# 06_-_PERIPHERALS_A.net
KiCad netlist of a schematic drawn in Altium Designer
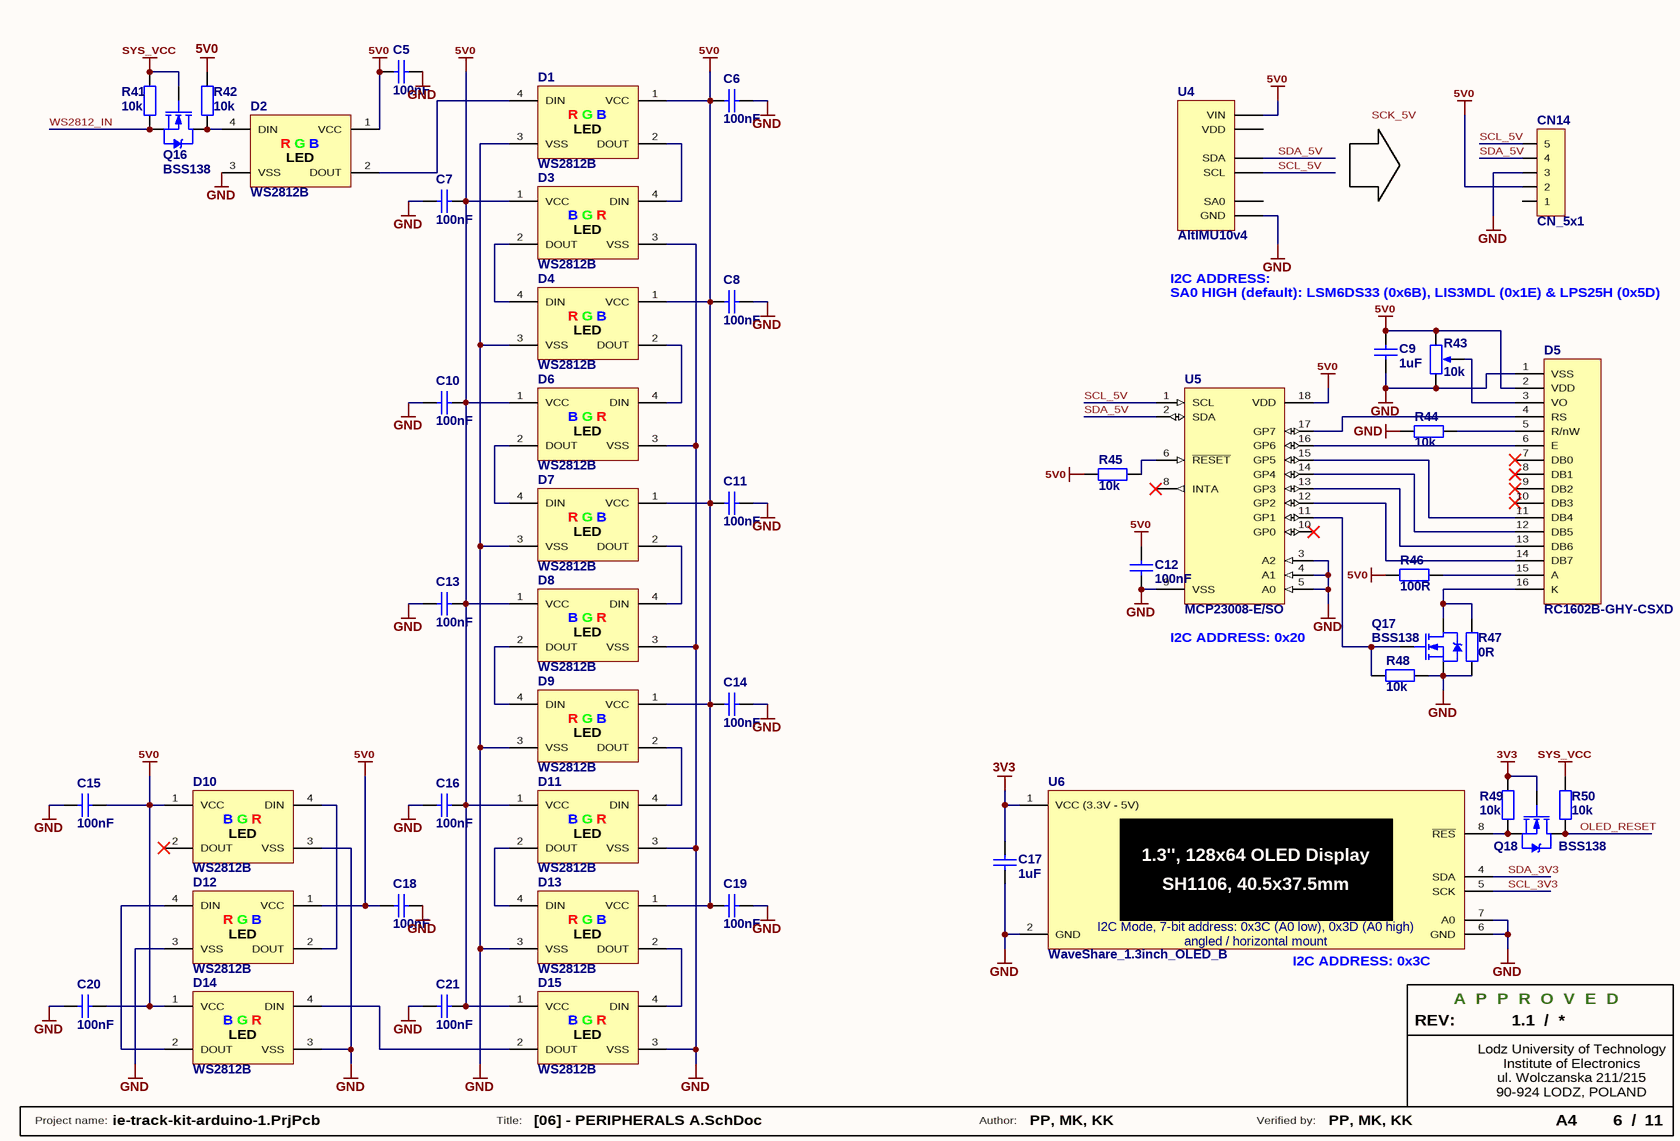
[diagram p0: [06] - PERIPHERALS A.SchDoc]

(export (version "E")
  (design (tool "Eeschema 10.0.6"))
  (components
    (comp (ref "C5")
      (value "100nF")
      (footprint "C0805")
      (description "Capacitor")
      (libsource (lib "capacitors") (part "Cap"))
    )
    (comp (ref "C6")
      (value "100nF")
      (footprint "C0805")
      (description "Capacitor")
      (libsource (lib "capacitors") (part "Cap"))
    )
    (comp (ref "C7")
      (value "100nF")
      (footprint "C0805")
      (description "Capacitor")
      (libsource (lib "capacitors") (part "Cap"))
    )
    (comp (ref "C8")
      (value "100nF")
      (footprint "C0805")
      (description "Capacitor")
      (libsource (lib "capacitors") (part "Cap"))
    )
    (comp (ref "C9")
      (value "1uF")
      (footprint "C0805")
      (description "Capacitor")
      (libsource (lib "capacitors") (part "Cap"))
    )
    (comp (ref "C10")
      (value "100nF")
      (footprint "C0805")
      (description "Capacitor")
      (libsource (lib "capacitors") (part "Cap"))
    )
    (comp (ref "C11")
      (value "100nF")
      (footprint "C0805")
      (description "Capacitor")
      (libsource (lib "capacitors") (part "Cap"))
    )
    (comp (ref "C12")
      (value "100nF")
      (footprint "C0805")
      (description "Capacitor")
      (libsource (lib "capacitors") (part "Cap"))
    )
    (comp (ref "C13")
      (value "100nF")
      (footprint "C0805")
      (description "Capacitor")
      (libsource (lib "capacitors") (part "Cap"))
    )
    (comp (ref "C14")
      (value "100nF")
      (footprint "C0805")
      (description "Capacitor")
      (libsource (lib "capacitors") (part "Cap"))
    )
    (comp (ref "C15")
      (value "100nF")
      (footprint "C0805")
      (description "Capacitor")
      (libsource (lib "capacitors") (part "Cap"))
    )
    (comp (ref "C16")
      (value "100nF")
      (footprint "C0805")
      (description "Capacitor")
      (libsource (lib "capacitors") (part "Cap"))
    )
    (comp (ref "C17")
      (value "1uF")
      (footprint "C0805")
      (description "Capacitor")
      (libsource (lib "capacitors") (part "Cap"))
    )
    (comp (ref "C18")
      (value "100nF")
      (footprint "C0805")
      (description "Capacitor")
      (libsource (lib "capacitors") (part "Cap"))
    )
    (comp (ref "C19")
      (value "100nF")
      (footprint "C0805")
      (description "Capacitor")
      (libsource (lib "capacitors") (part "Cap"))
    )
    (comp (ref "C20")
      (value "100nF")
      (footprint "C0805")
      (description "Capacitor")
      (libsource (lib "capacitors") (part "Cap"))
    )
    (comp (ref "C21")
      (value "100nF")
      (footprint "C0805")
      (description "Capacitor")
      (libsource (lib "capacitors") (part "Cap"))
    )
    (comp (ref "CN14")
      (value "CN_5x1")
      (footprint "GP_5x1H_F")
      (libsource (lib "goldpin_female") (part "CN_5x1"))
    )
    (comp (ref "D1")
      (value "WS2812B")
      (footprint "WS2812B")
      (description "Intelligent control LED integrated light source")
      (libsource (lib "leds") (part "WS2812B"))
    )
    (comp (ref "D2")
      (value "WS2812B")
      (footprint "WS2812B")
      (description "Intelligent control LED integrated light source")
      (libsource (lib "leds") (part "WS2812B"))
    )
    (comp (ref "D3")
      (value "WS2812B")
      (footprint "WS2812B")
      (description "Intelligent control LED integrated light source")
      (libsource (lib "") (part "WS2812B_1"))
    )
    (comp (ref "D4")
      (value "WS2812B")
      (footprint "WS2812B")
      (description "Intelligent control LED integrated light source")
      (libsource (lib "leds") (part "WS2812B"))
    )
    (comp (ref "D5")
      (value "RC1602B-GHY-CSXD")
      (footprint "RC1602B-GHY-CSXD")
      (description "16x2 LCD Display")
      (libsource (lib "lcd_displays") (part "RC1602B-GHY-CSXD"))
    )
    (comp (ref "D6")
      (value "WS2812B")
      (footprint "WS2812B")
      (description "Intelligent control LED integrated light source")
      (libsource (lib "") (part "WS2812B_1"))
    )
    (comp (ref "D7")
      (value "WS2812B")
      (footprint "WS2812B")
      (description "Intelligent control LED integrated light source")
      (libsource (lib "leds") (part "WS2812B"))
    )
    (comp (ref "D8")
      (value "WS2812B")
      (footprint "WS2812B")
      (description "Intelligent control LED integrated light source")
      (libsource (lib "") (part "WS2812B_1"))
    )
    (comp (ref "D9")
      (value "WS2812B")
      (footprint "WS2812B")
      (description "Intelligent control LED integrated light source")
      (libsource (lib "leds") (part "WS2812B"))
    )
    (comp (ref "D10")
      (value "WS2812B")
      (footprint "WS2812B")
      (description "Intelligent control LED integrated light source")
      (libsource (lib "") (part "WS2812B_1"))
    )
    (comp (ref "D11")
      (value "WS2812B")
      (footprint "WS2812B")
      (description "Intelligent control LED integrated light source")
      (libsource (lib "") (part "WS2812B_1"))
    )
    (comp (ref "D12")
      (value "WS2812B")
      (footprint "WS2812B")
      (description "Intelligent control LED integrated light source")
      (libsource (lib "leds") (part "WS2812B"))
    )
    (comp (ref "D13")
      (value "WS2812B")
      (footprint "WS2812B")
      (description "Intelligent control LED integrated light source")
      (libsource (lib "leds") (part "WS2812B"))
    )
    (comp (ref "D14")
      (value "WS2812B")
      (footprint "WS2812B")
      (description "Intelligent control LED integrated light source")
      (libsource (lib "") (part "WS2812B_1"))
    )
    (comp (ref "D15")
      (value "WS2812B")
      (footprint "WS2812B")
      (description "Intelligent control LED integrated light source")
      (libsource (lib "") (part "WS2812B_1"))
    )
    (comp (ref "Q16")
      (value "BSS138")
      (footprint "SOT-23")
      (description "N-Channel Enhancement Mode Vertical DMOS FET")
      (fields (field (name "PUBLISHER") "Altium Limited"))
      (libsource (lib "transistors_other") (part "BSS138"))
    )
    (comp (ref "Q17")
      (value "BSS138")
      (footprint "SOT-23")
      (description "N-Channel Enhancement Mode Vertical DMOS FET")
      (fields (field (name "PUBLISHER") "Altium Limited"))
      (libsource (lib "transistors_other") (part "BSS138"))
    )
    (comp (ref "Q18")
      (value "BSS138")
      (footprint "SOT-23")
      (description "N-Channel Enhancement Mode Vertical DMOS FET")
      (fields (field (name "PUBLISHER") "Altium Limited"))
      (libsource (lib "transistors_other") (part "BSS138"))
    )
    (comp (ref "R41")
      (value "10k")
      (footprint "R0805")
      (description "Resistor")
      (libsource (lib "") (part "Res_2"))
    )
    (comp (ref "R42")
      (value "10k")
      (footprint "R0805")
      (description "Resistor")
      (libsource (lib "") (part "Res_2"))
    )
    (comp (ref "R43")
      (value "10k")
      (footprint "3305SMD")
      (description "3305SMD-10K")
      (libsource (lib "resistors") (part "3305SMD-10K"))
    )
    (comp (ref "R44")
      (value "10k")
      (footprint "R0805")
      (description "Resistor")
      (libsource (lib "resistors") (part "Res"))
    )
    (comp (ref "R45")
      (value "10k")
      (footprint "R0805")
      (description "Resistor")
      (libsource (lib "resistors") (part "Res"))
    )
    (comp (ref "R46")
      (value "100R")
      (footprint "R0805")
      (description "Resistor")
      (libsource (lib "resistors") (part "Res"))
    )
    (comp (ref "R47")
      (value "0R")
      (footprint "R0805")
      (description "Resistor")
      (libsource (lib "") (part "Res_1"))
    )
    (comp (ref "R48")
      (value "10k")
      (footprint "R0805")
      (description "Resistor")
      (libsource (lib "resistors") (part "Res"))
    )
    (comp (ref "R49")
      (value "10k")
      (footprint "R0805")
      (description "Resistor")
      (libsource (lib "") (part "Res_2"))
    )
    (comp (ref "R50")
      (value "10k")
      (footprint "R0805")
      (description "Resistor")
      (libsource (lib "") (part "Res_2"))
    )
    (comp (ref "U4")
      (value "AltIMU10v4")
      (footprint "AltIMU-10 v4_REVERSE")
      (description "Pololu Gyro, Accelerometer, Compass, and Altimeter (L3GD20H, LSM303D, and LPS25H Carrier)")
      (libsource (lib "mems_and_imu_modules") (part "AltIMU10v4"))
    )
    (comp (ref "U5")
      (value "MCP23008-E/SO")
      (footprint "SO18W")
      (description "8-Bit I/O Expander with Serial Interface I2C, 18-Pin SOIC Package")
      (libsource (lib "io_expanders") (part "MCP23008-E/SO"))
    )
    (comp (ref "U6")
      (value "WaveShare_1.3inch_OLED_B")
      (footprint "WaveShare_1.3INCH_OLED")
      (description "DEP096032B-W OLED Display")
      (libsource (lib "oled_displays") (part "WaveShare_1.3inch_OLED"))
    )
  )
  (nets
    (net (code "1") (name "/OLED_RESET") (class "Default")
      (node (ref "Q18") (pin "3") (pinfunction "D_3") (pintype "passive"))
      (node (ref "R50") (pin "1") (pinfunction "1_1") (pintype "passive"))
    )
    (net (code "3") (name "/SCL_3V3") (class "Default")
      (node (ref "U6") (pin "5") (pinfunction "SCK_5") (pintype "passive"))
    )
    (net (code "4") (name "/SCL_5V") (class "Default")
      (node (ref "CN14") (pin "5") (pinfunction "5_5") (pintype "passive"))
      (node (ref "U4") (pin "6") (pinfunction "SCL_6") (pintype "passive"))
      (node (ref "U5") (pin "1") (pinfunction "SCL_1") (pintype "input"))
    )
    (net (code "5") (name "/SDA_3V3") (class "Default")
      (node (ref "U6") (pin "4") (pinfunction "SDA_4") (pintype "passive"))
    )
    (net (code "6") (name "/SDA_5V") (class "Default")
      (node (ref "CN14") (pin "4") (pinfunction "4_4") (pintype "passive"))
      (node (ref "U4") (pin "5") (pinfunction "SDA_5") (pintype "passive"))
      (node (ref "U5") (pin "2") (pinfunction "SDA_2") (pintype "bidirectional"))
    )
    (net (code "7") (name "/WS2812_IN") (class "Default")
      (node (ref "Q16") (pin "2") (pinfunction "S_2") (pintype "passive"))
      (node (ref "R41") (pin "1") (pinfunction "1_1") (pintype "passive"))
    )
    (net (code "8") (name "3V3") (class "Default")
      (node (ref "C17") (pin "2") (pinfunction "2_2") (pintype "passive"))
      (node (ref "Q18") (pin "1") (pinfunction "G_1") (pintype "passive"))
      (node (ref "R49") (pin "2") (pinfunction "2_2") (pintype "passive"))
      (node (ref "U6") (pin "1") (pinfunction "VCC_(3.3V_-_5V)_1") (pintype "passive"))
    )
    (net (code "9") (name "5V0") (class "Default")
      (node (ref "C10") (pin "2") (pinfunction "2_2") (pintype "passive"))
      (node (ref "C11") (pin "1") (pinfunction "1_1") (pintype "passive"))
      (node (ref "C12") (pin "2") (pinfunction "2_2") (pintype "passive"))
      (node (ref "C13") (pin "2") (pinfunction "2_2") (pintype "passive"))
      (node (ref "C14") (pin "1") (pinfunction "1_1") (pintype "passive"))
      (node (ref "C15") (pin "2") (pinfunction "2_2") (pintype "passive"))
      (node (ref "C16") (pin "2") (pinfunction "2_2") (pintype "passive"))
      (node (ref "C18") (pin "1") (pinfunction "1_1") (pintype "passive"))
      (node (ref "C19") (pin "1") (pinfunction "1_1") (pintype "passive"))
      (node (ref "C20") (pin "2") (pinfunction "2_2") (pintype "passive"))
      (node (ref "C21") (pin "2") (pinfunction "2_2") (pintype "passive"))
      (node (ref "C5") (pin "1") (pinfunction "1_1") (pintype "passive"))
      (node (ref "C6") (pin "1") (pinfunction "1_1") (pintype "passive"))
      (node (ref "C7") (pin "2") (pinfunction "2_2") (pintype "passive"))
      (node (ref "C8") (pin "1") (pinfunction "1_1") (pintype "passive"))
      (node (ref "C9") (pin "2") (pinfunction "2_2") (pintype "passive"))
      (node (ref "CN14") (pin "2") (pinfunction "2_2") (pintype "passive"))
      (node (ref "D1") (pin "1") (pinfunction "VCC_1") (pintype "power_in"))
      (node (ref "D10") (pin "1") (pinfunction "VCC_1") (pintype "power_in"))
      (node (ref "D11") (pin "1") (pinfunction "VCC_1") (pintype "power_in"))
      (node (ref "D12") (pin "1") (pinfunction "VCC_1") (pintype "power_in"))
      (node (ref "D13") (pin "1") (pinfunction "VCC_1") (pintype "power_in"))
      (node (ref "D14") (pin "1") (pinfunction "VCC_1") (pintype "power_in"))
      (node (ref "D15") (pin "1") (pinfunction "VCC_1") (pintype "power_in"))
      (node (ref "D2") (pin "1") (pinfunction "VCC_1") (pintype "power_in"))
      (node (ref "D3") (pin "1") (pinfunction "VCC_1") (pintype "power_in"))
      (node (ref "D4") (pin "1") (pinfunction "VCC_1") (pintype "power_in"))
      (node (ref "D5") (pin "2") (pinfunction "VDD_2") (pintype "power_in"))
      (node (ref "D6") (pin "1") (pinfunction "VCC_1") (pintype "power_in"))
      (node (ref "D7") (pin "1") (pinfunction "VCC_1") (pintype "power_in"))
      (node (ref "D8") (pin "1") (pinfunction "VCC_1") (pintype "power_in"))
      (node (ref "D9") (pin "1") (pinfunction "VCC_1") (pintype "power_in"))
      (node (ref "R42") (pin "2") (pinfunction "2_2") (pintype "passive"))
      (node (ref "R43") (pin "1") (pinfunction "TOP_1") (pintype "passive"))
      (node (ref "R45") (pin "1") (pinfunction "1_1") (pintype "passive"))
      (node (ref "R46") (pin "1") (pinfunction "1_1") (pintype "passive"))
      (node (ref "U4") (pin "3") (pinfunction "VIN_3") (pintype "passive"))
      (node (ref "U5") (pin "18") (pinfunction "VDD_18") (pintype "power_in"))
    )
    (net (code "10") (name "GND") (class "Default")
      (node (ref "C10") (pin "1") (pinfunction "1_1") (pintype "passive"))
      (node (ref "C11") (pin "2") (pinfunction "2_2") (pintype "passive"))
      (node (ref "C12") (pin "1") (pinfunction "1_1") (pintype "passive"))
      (node (ref "C13") (pin "1") (pinfunction "1_1") (pintype "passive"))
      (node (ref "C14") (pin "2") (pinfunction "2_2") (pintype "passive"))
      (node (ref "C15") (pin "1") (pinfunction "1_1") (pintype "passive"))
      (node (ref "C16") (pin "1") (pinfunction "1_1") (pintype "passive"))
      (node (ref "C17") (pin "1") (pinfunction "1_1") (pintype "passive"))
      (node (ref "C18") (pin "2") (pinfunction "2_2") (pintype "passive"))
      (node (ref "C19") (pin "2") (pinfunction "2_2") (pintype "passive"))
      (node (ref "C20") (pin "1") (pinfunction "1_1") (pintype "passive"))
      (node (ref "C21") (pin "1") (pinfunction "1_1") (pintype "passive"))
      (node (ref "C5") (pin "2") (pinfunction "2_2") (pintype "passive"))
      (node (ref "C6") (pin "2") (pinfunction "2_2") (pintype "passive"))
      (node (ref "C7") (pin "1") (pinfunction "1_1") (pintype "passive"))
      (node (ref "C8") (pin "2") (pinfunction "2_2") (pintype "passive"))
      (node (ref "C9") (pin "1") (pinfunction "1_1") (pintype "passive"))
      (node (ref "CN14") (pin "3") (pinfunction "3_3") (pintype "passive"))
      (node (ref "D1") (pin "3") (pinfunction "VSS_3") (pintype "power_in"))
      (node (ref "D10") (pin "3") (pinfunction "VSS_3") (pintype "power_in"))
      (node (ref "D11") (pin "3") (pinfunction "VSS_3") (pintype "power_in"))
      (node (ref "D12") (pin "3") (pinfunction "VSS_3") (pintype "power_in"))
      (node (ref "D13") (pin "3") (pinfunction "VSS_3") (pintype "power_in"))
      (node (ref "D14") (pin "3") (pinfunction "VSS_3") (pintype "power_in"))
      (node (ref "D15") (pin "3") (pinfunction "VSS_3") (pintype "power_in"))
      (node (ref "D2") (pin "3") (pinfunction "VSS_3") (pintype "power_in"))
      (node (ref "D3") (pin "3") (pinfunction "VSS_3") (pintype "power_in"))
      (node (ref "D4") (pin "3") (pinfunction "VSS_3") (pintype "power_in"))
      (node (ref "D5") (pin "1") (pinfunction "VSS_1") (pintype "power_in"))
      (node (ref "D6") (pin "3") (pinfunction "VSS_3") (pintype "power_in"))
      (node (ref "D7") (pin "3") (pinfunction "VSS_3") (pintype "power_in"))
      (node (ref "D8") (pin "3") (pinfunction "VSS_3") (pintype "power_in"))
      (node (ref "D9") (pin "3") (pinfunction "VSS_3") (pintype "power_in"))
      (node (ref "Q17") (pin "2") (pinfunction "S_2") (pintype "passive"))
      (node (ref "R43") (pin "2") (pinfunction "BOT_2") (pintype "passive"))
      (node (ref "R44") (pin "1") (pinfunction "1_1") (pintype "passive"))
      (node (ref "R47") (pin "2") (pinfunction "2_2") (pintype "passive"))
      (node (ref "R48") (pin "2") (pinfunction "2_2") (pintype "passive"))
      (node (ref "U4") (pin "1") (pinfunction "GND_1") (pintype "passive"))
      (node (ref "U5") (pin "3") (pinfunction "A2_3") (pintype "input"))
      (node (ref "U5") (pin "4") (pinfunction "A1_4") (pintype "input"))
      (node (ref "U5") (pin "5") (pinfunction "A0_5") (pintype "input"))
      (node (ref "U5") (pin "9") (pinfunction "VSS_9") (pintype "power_in"))
      (node (ref "U6") (pin "2") (pinfunction "GND_2") (pintype "passive"))
      (node (ref "U6") (pin "6") (pinfunction "GND_6") (pintype "passive"))
      (node (ref "U6") (pin "7") (pinfunction "A0_7") (pintype "passive"))
    )
    (net (code "11") (name "Net-(D1-DIN)") (class "Default")
      (node (ref "D1") (pin "4") (pinfunction "DIN_4") (pintype "power_in"))
      (node (ref "D2") (pin "2") (pinfunction "DOUT_2") (pintype "power_in"))
    )
    (net (code "12") (name "Net-(D1-DOUT)") (class "Default")
      (node (ref "D1") (pin "2") (pinfunction "DOUT_2") (pintype "power_in"))
      (node (ref "D3") (pin "4") (pinfunction "DIN_4") (pintype "power_in"))
    )
    (net (code "13") (name "Net-(D2-DIN)") (class "Default")
      (node (ref "D2") (pin "4") (pinfunction "DIN_4") (pintype "power_in"))
      (node (ref "Q16") (pin "3") (pinfunction "D_3") (pintype "passive"))
      (node (ref "R42") (pin "1") (pinfunction "1_1") (pintype "passive"))
    )
    (net (code "14") (name "Net-(D3-DOUT)") (class "Default")
      (node (ref "D3") (pin "2") (pinfunction "DOUT_2") (pintype "power_in"))
      (node (ref "D4") (pin "4") (pinfunction "DIN_4") (pintype "power_in"))
    )
    (net (code "15") (name "Net-(D4-DOUT)") (class "Default")
      (node (ref "D4") (pin "2") (pinfunction "DOUT_2") (pintype "power_in"))
      (node (ref "D6") (pin "4") (pinfunction "DIN_4") (pintype "power_in"))
    )
    (net (code "16") (name "Net-(D5-A)") (class "Default")
      (node (ref "D5") (pin "15") (pinfunction "A_15") (pintype "power_in"))
      (node (ref "R46") (pin "2") (pinfunction "2_2") (pintype "passive"))
    )
    (net (code "17") (name "Net-(D5-DB4)") (class "Default")
      (node (ref "D5") (pin "11") (pinfunction "DB4_11") (pintype "power_in"))
      (node (ref "U5") (pin "15") (pinfunction "GP5_15") (pintype "bidirectional"))
    )
    (net (code "18") (name "Net-(D5-DB5)") (class "Default")
      (node (ref "D5") (pin "12") (pinfunction "DB5_12") (pintype "power_in"))
      (node (ref "U5") (pin "14") (pinfunction "GP4_14") (pintype "bidirectional"))
    )
    (net (code "19") (name "Net-(D5-DB6)") (class "Default")
      (node (ref "D5") (pin "13") (pinfunction "DB6_13") (pintype "power_in"))
      (node (ref "U5") (pin "13") (pinfunction "GP3_13") (pintype "bidirectional"))
    )
    (net (code "20") (name "Net-(D5-DB7)") (class "Default")
      (node (ref "D5") (pin "14") (pinfunction "DB7_14") (pintype "power_in"))
      (node (ref "U5") (pin "12") (pinfunction "GP2_12") (pintype "bidirectional"))
    )
    (net (code "21") (name "Net-(D5-E)") (class "Default")
      (node (ref "D5") (pin "6") (pinfunction "E_6") (pintype "power_in"))
      (node (ref "U5") (pin "16") (pinfunction "GP6_16") (pintype "bidirectional"))
    )
    (net (code "22") (name "Net-(D5-K)") (class "Default")
      (node (ref "D5") (pin "16") (pinfunction "K_16") (pintype "power_in"))
      (node (ref "Q17") (pin "3") (pinfunction "D_3") (pintype "passive"))
      (node (ref "R47") (pin "1") (pinfunction "1_1") (pintype "passive"))
    )
    (net (code "23") (name "Net-(D5-RS)") (class "Default")
      (node (ref "D5") (pin "4") (pinfunction "RS_4") (pintype "power_in"))
      (node (ref "U5") (pin "17") (pinfunction "GP7_17") (pintype "bidirectional"))
    )
    (net (code "24") (name "Net-(D5-R{slash}nW)") (class "Default")
      (node (ref "D5") (pin "5") (pinfunction "R/nW_5") (pintype "power_in"))
      (node (ref "R44") (pin "2") (pinfunction "2_2") (pintype "passive"))
    )
    (net (code "25") (name "Net-(D5-VO)") (class "Default")
      (node (ref "D5") (pin "3") (pinfunction "VO_3") (pintype "power_in"))
      (node (ref "R43") (pin "3") (pinfunction "TAP_3") (pintype "passive"))
    )
    (net (code "26") (name "Net-(D6-DOUT)") (class "Default")
      (node (ref "D6") (pin "2") (pinfunction "DOUT_2") (pintype "power_in"))
      (node (ref "D7") (pin "4") (pinfunction "DIN_4") (pintype "power_in"))
    )
    (net (code "27") (name "Net-(D7-DOUT)") (class "Default")
      (node (ref "D7") (pin "2") (pinfunction "DOUT_2") (pintype "power_in"))
      (node (ref "D8") (pin "4") (pinfunction "DIN_4") (pintype "power_in"))
    )
    (net (code "28") (name "Net-(D8-DOUT)") (class "Default")
      (node (ref "D8") (pin "2") (pinfunction "DOUT_2") (pintype "power_in"))
      (node (ref "D9") (pin "4") (pinfunction "DIN_4") (pintype "power_in"))
    )
    (net (code "29") (name "Net-(D10-DIN)") (class "Default")
      (node (ref "D10") (pin "4") (pinfunction "DIN_4") (pintype "power_in"))
      (node (ref "D12") (pin "2") (pinfunction "DOUT_2") (pintype "power_in"))
    )
    (net (code "30") (name "Net-(D11-DIN)") (class "Default")
      (node (ref "D11") (pin "4") (pinfunction "DIN_4") (pintype "power_in"))
      (node (ref "D9") (pin "2") (pinfunction "DOUT_2") (pintype "power_in"))
    )
    (net (code "31") (name "Net-(D11-DOUT)") (class "Default")
      (node (ref "D11") (pin "2") (pinfunction "DOUT_2") (pintype "power_in"))
      (node (ref "D13") (pin "4") (pinfunction "DIN_4") (pintype "power_in"))
    )
    (net (code "32") (name "Net-(D12-DIN)") (class "Default")
      (node (ref "D12") (pin "4") (pinfunction "DIN_4") (pintype "power_in"))
      (node (ref "D14") (pin "2") (pinfunction "DOUT_2") (pintype "power_in"))
    )
    (net (code "33") (name "Net-(D13-DOUT)") (class "Default")
      (node (ref "D13") (pin "2") (pinfunction "DOUT_2") (pintype "power_in"))
      (node (ref "D15") (pin "4") (pinfunction "DIN_4") (pintype "power_in"))
    )
    (net (code "34") (name "Net-(D14-DIN)") (class "Default")
      (node (ref "D14") (pin "4") (pinfunction "DIN_4") (pintype "power_in"))
      (node (ref "D15") (pin "2") (pinfunction "DOUT_2") (pintype "power_in"))
    )
    (net (code "35") (name "Net-(Q17-G)") (class "Default")
      (node (ref "Q17") (pin "1") (pinfunction "G_1") (pintype "passive"))
      (node (ref "R48") (pin "1") (pinfunction "1_1") (pintype "passive"))
      (node (ref "U5") (pin "11") (pinfunction "GP1_11") (pintype "bidirectional"))
    )
    (net (code "36") (name "Net-(Q18-S)") (class "Default")
      (node (ref "Q18") (pin "2") (pinfunction "S_2") (pintype "passive"))
      (node (ref "R49") (pin "1") (pinfunction "1_1") (pintype "passive"))
      (node (ref "U6") (pin "8") (pinfunction "~{RES}_8") (pintype "passive"))
    )
    (net (code "37") (name "Net-(U5-~{RESET})") (class "Default")
      (node (ref "R45") (pin "2") (pinfunction "2_2") (pintype "passive"))
      (node (ref "U5") (pin "6") (pinfunction "~{RESET}_6") (pintype "input"))
    )
    (net (code "38") (name "SYS_VCC") (class "Default")
      (node (ref "Q16") (pin "1") (pinfunction "G_1") (pintype "passive"))
      (node (ref "R41") (pin "2") (pinfunction "2_2") (pintype "passive"))
      (node (ref "R50") (pin "2") (pinfunction "2_2") (pintype "passive"))
    )
    (net (code "39") (name "unconnected-(CN14-Pad1)") (class "Default")
      (node (ref "CN14") (pin "1") (pinfunction "1_1") (pintype "passive"))
    )
    (net (code "40") (name "unconnected-(D5-DB0-Pad7)") (class "Default")
      (node (ref "D5") (pin "7") (pinfunction "DB0_7") (pintype "power_in+no_connect"))
    )
    (net (code "41") (name "unconnected-(D5-DB1-Pad8)") (class "Default")
      (node (ref "D5") (pin "8") (pinfunction "DB1_8") (pintype "power_in+no_connect"))
    )
    (net (code "42") (name "unconnected-(D5-DB2-Pad9)") (class "Default")
      (node (ref "D5") (pin "9") (pinfunction "DB2_9") (pintype "power_in+no_connect"))
    )
    (net (code "43") (name "unconnected-(D5-DB3-Pad10)") (class "Default")
      (node (ref "D5") (pin "10") (pinfunction "DB3_10") (pintype "power_in+no_connect"))
    )
    (net (code "44") (name "unconnected-(D10-DOUT-Pad2)") (class "Default")
      (node (ref "D10") (pin "2") (pinfunction "DOUT_2") (pintype "power_in+no_connect"))
    )
    (net (code "45") (name "unconnected-(U4-SA0-Pad2)") (class "Default")
      (node (ref "U4") (pin "2") (pinfunction "SA0_2") (pintype "passive"))
    )
    (net (code "46") (name "unconnected-(U4-VDD-Pad4)") (class "Default")
      (node (ref "U4") (pin "4") (pinfunction "VDD_4") (pintype "passive"))
    )
    (net (code "47") (name "unconnected-(U5-GP0-Pad10)") (class "Default")
      (node (ref "U5") (pin "10") (pinfunction "GP0_10") (pintype "bidirectional+no_connect"))
    )
    (net (code "48") (name "unconnected-(U5-INTA-Pad8)") (class "Default")
      (node (ref "U5") (pin "8") (pinfunction "INTA_8") (pintype "output+no_connect"))
    )
  )
)
